# Schematic1_2.net
KiCad netlist of a schematic drawn in Altium Designer
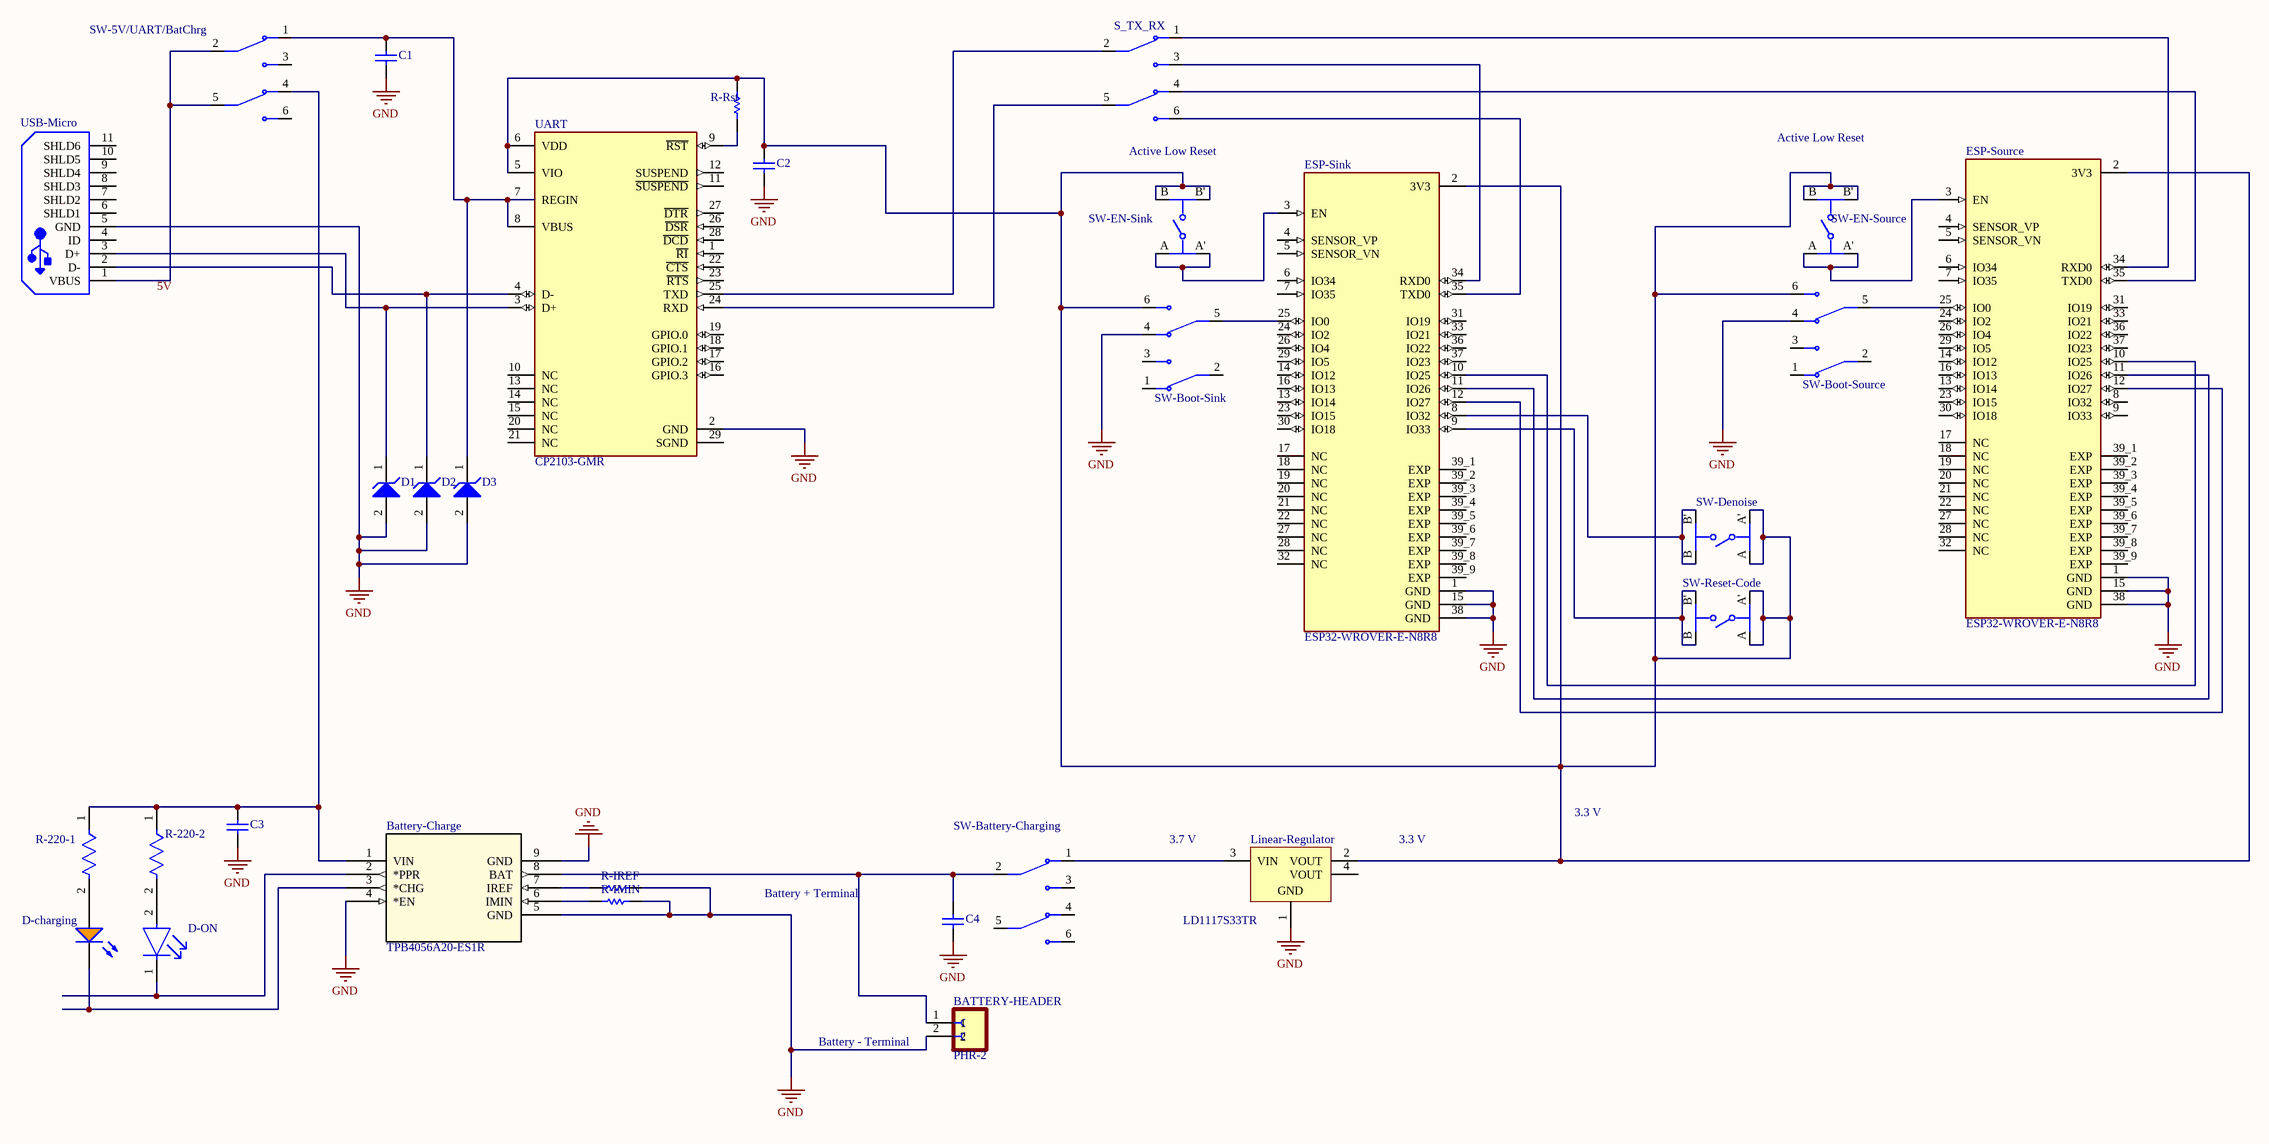
[diagram p0: Schematic1.2.SchDoc]

(export (version "E")
  (design (tool "Eeschema 10.0.6"))
  (components
    (comp (ref "Battery-Charge")
      (value "TPB4056A20-ES1R")
      (footprint "ESOP-8_TPK")
      (description "No Description Available")
      (libsource (lib "TPB4056A20-ES1R") (part "TPB4056A20-ES1R"))
    )
    (comp (ref "BATTERY-HEADER")
      (value "PHR-2")
      (footprint "FP-PHR-2-MFG")
      (description "PH Series 2 Position 2 mm Pitch Free Hanging Housing Connector")
      (libsource (lib "Ninos Rihan") (part "PHR-2"))
    )
    (comp (ref "C1")
      (value "C0603C105K3RACTU")
      (footprint "CAPC1608X87X35LL15T15")
      (fields (field (name "MANUFACTURER") "Kemet"))
      (libsource (lib "Altium Content Vault") (part "CAP"))
    )
    (comp (ref "C2")
      (value "C0603C105K3RACTU")
      (footprint "CAPC1608X87X35LL15T15")
      (fields (field (name "MANUFACTURER") "Kemet"))
      (libsource (lib "Altium Content Vault") (part "CAP"))
    )
    (comp (ref "C3")
      (value "C0603C105K3RACTU")
      (footprint "CAPC1608X87X35LL15T15")
      (fields (field (name "MANUFACTURER") "Kemet"))
      (libsource (lib "Altium Content Vault") (part "CAP"))
    )
    (comp (ref "C4")
      (value "C0603C105K3RACTU")
      (footprint "CAPC1608X87X35LL15T15")
      (fields (field (name "MANUFACTURER") "Kemet"))
      (libsource (lib "Altium Content Vault") (part "CAP"))
    )
    (comp (ref "D-charging")
      (value "LTST-C190AKT")
      (footprint "LTST-C190AKT-2_V")
      (description "Single Color Chip LED, 2.1 V, 2 mcd, -55 to 85 degC, 2-Pin SMD, RoHS, Tape and Reel")
      (libsource (lib "Altium Content Vault") (part "LED-ORANGE-AK-2"))
    )
    (comp (ref "D-ON")
      (value "LTST-C190GKT")
      (footprint "FP-LTST-C190GKT-MFG")
      (description "LED GREEN CLEAR CHIP SMD")
      (fields (field (name "VOLTAGE") "2V"))
      (libsource (lib "Altium Content Vault") (part "8706943c75ba83719d021d2fdc84c58"))
    )
    (comp (ref "D1")
      (value "MMSZ4691T1G")
      (footprint "ONSC-SOD-123-2-425-04_V")
      (description "Zener Voltage Regulator, 500 mW, 2-Pin SOD-123, Pb-Free, Tape and Reel")
      (fields (field (name "MANUFACTURER") "On Semiconductor"))
      (libsource (lib "Altium Content Vault") (part "ONSC-K1A2-2"))
    )
    (comp (ref "D2")
      (value "MMSZ4691T1G")
      (footprint "ONSC-SOD-123-2-425-04_V")
      (description "Zener Voltage Regulator, 500 mW, 2-Pin SOD-123, Pb-Free, Tape and Reel")
      (fields (field (name "MANUFACTURER") "On Semiconductor"))
      (libsource (lib "Altium Content Vault") (part "ONSC-K1A2-2"))
    )
    (comp (ref "D3")
      (value "MMSZ4691T1G")
      (footprint "ONSC-SOD-123-2-425-04_V")
      (description "Zener Voltage Regulator, 500 mW, 2-Pin SOD-123, Pb-Free, Tape and Reel")
      (fields (field (name "MANUFACTURER") "On Semiconductor"))
      (libsource (lib "Altium Content Vault") (part "ONSC-K1A2-2"))
    )
    (comp (ref "ESP-Sink")
      (value "ESP32-WROVER-E-N8R8")
      (footprint "XCVR_ESP32-WROVER-E-N8R8")
      (libsource (lib "Ninos Rihan") (part "ESP32-WROVER-E-N8R8"))
    )
    (comp (ref "ESP-Source")
      (value "ESP32-WROVER-E-N8R8")
      (footprint "XCVR_ESP32-WROVER-E-N8R8")
      (libsource (lib "Ninos Rihan") (part "ESP32-WROVER-E-N8R8"))
    )
    (comp (ref "Linear-Regulator")
      (value "LD1117S33TR")
      (footprint "SOT-223_L")
      (description "Fixed Low Drop Positive Voltage Regulator, 3.3V, 4-Pin SOT-223, Tape and Reel")
      (libsource (lib "Altium Content Vault") (part "PM-REG-LD1117-SOT4"))
    )
    (comp (ref "R-220-1")
      (value "CRCW0603220RFKEA")
      (footprint "FP-CRCW0603-e3-MFG")
      (description "RES Thick Film, 220Ω, 1%, 0.1W, 100ppm/°C, 0603")
      (fields (field (name "TOLERANCE") "1%"))
      (libsource (lib "Altium Content Vault") (part "1029c3af85768c4190bb7ad29bc67b5"))
    )
    (comp (ref "R-220-2")
      (value "CRCW0603220RFKEA")
      (footprint "FP-CRCW0603-e3-MFG")
      (description "RES Thick Film, 220Ω, 1%, 0.1W, 100ppm/°C, 0603")
      (fields (field (name "TOLERANCE") "1%"))
      (libsource (lib "Altium Content Vault") (part "1029c3af85768c4190bb7ad29bc67b5"))
    )
    (comp (ref "R-IMIN")
      (value "CRCW0805100KJNEA")
      (footprint "RESC2013X50X30ML20T20")
      (fields
        (field (name "MANUFACTURER") "Vishay Dale")
        (field (name "TOLERANCE") "5%")
        (field (name "POWER") "125mW")
      )
      (libsource (lib "Altium Content Vault") (part "RES"))
    )
    (comp (ref "R-IREF")
      (value "ERJ-3EKF1301V")
      (footprint "RESC1608X55X30NL15T15")
      (fields
        (field (name "MANUFACTURER") "Panasonic")
        (field (name "TOLERANCE") "1%")
        (field (name "POWER") "100mW")
      )
      (libsource (lib "Altium Content Vault") (part "RES"))
    )
    (comp (ref "R-Rst")
      (value "RC0603FR-074K7L")
      (footprint "RESC1608X55X25LL10T15")
      (description "Chip Resistor, 4.7 KOhm, +/- 1%, 0.1 W, -55 to 155 degC, 0603 (1608 Metric), RoHS, Tape and Reel")
      (fields (field (name "MANUFACTURER") "Yageo") (field (name "TOLERANCE") "1%"))
      (libsource (lib "Altium Content Vault") (part "RES-2"))
    )
    (comp (ref "SW-5V/UART/BatChrg")
      (value "SLW-913535-2A-SMT")
      (footprint "SW_SLW-913535-2A-SMT")
      (description "Switch Slide ON ON DPDT Raised Slide 0.1A 12VDC 10000Cycles Gull Wing SMD Box")
      (libsource (lib "Ninos Rihan") (part "SLW-913535-2A-SMT"))
    )
    (comp (ref "SW-Battery-Charging")
      (value "SLW-913535-2A-SMT")
      (footprint "SW_SLW-913535-2A-SMT")
      (description "Switch Slide ON ON DPDT Raised Slide 0.1A 12VDC 10000Cycles Gull Wing SMD Box")
      (libsource (lib "Ninos Rihan") (part "SLW-913535-2A-SMT"))
    )
    (comp (ref "SW-Boot-Sink")
      (value "SLW-913535-2A-SMT")
      (footprint "SW_SLW-913535-2A-SMT")
      (description "Switch Slide ON ON DPDT Raised Slide 0.1A 12VDC 10000Cycles Gull Wing SMD Box")
      (libsource (lib "Ninos Rihan") (part "SLW-913535-2A-SMT"))
    )
    (comp (ref "SW-Boot-Source")
      (value "SLW-913535-2A-SMT")
      (footprint "SW_SLW-913535-2A-SMT")
      (description "Switch Slide ON ON DPDT Raised Slide 0.1A 12VDC 10000Cycles Gull Wing SMD Box")
      (libsource (lib "Ninos Rihan") (part "SLW-913535-2A-SMT"))
    )
    (comp (ref "SW-Denoise")
      (value "EVQ-Q2F03W")
      (footprint "FP-EVQ-Q2F03W-MFG")
      (description "SWITCH TACTILE SPST-NO 0.02A 15V")
      (libsource (lib "Altium Content Vault") (part "9677229990528492022b31d4503349f"))
    )
    (comp (ref "SW-EN-Sink")
      (value "EVQ-Q2F03W")
      (footprint "FP-EVQ-Q2F03W-MFG")
      (description "SWITCH TACTILE SPST-NO 0.02A 15V")
      (libsource (lib "Altium Content Vault") (part "9677229990528492022b31d4503349f"))
    )
    (comp (ref "SW-EN-Source")
      (value "EVQ-Q2F03W")
      (footprint "FP-EVQ-Q2F03W-MFG")
      (description "SWITCH TACTILE SPST-NO 0.02A 15V")
      (libsource (lib "Altium Content Vault") (part "9677229990528492022b31d4503349f"))
    )
    (comp (ref "SW-Reset-Code")
      (value "EVQ-Q2F03W")
      (footprint "FP-EVQ-Q2F03W-MFG")
      (description "SWITCH TACTILE SPST-NO 0.02A 15V")
      (libsource (lib "Altium Content Vault") (part "9677229990528492022b31d4503349f"))
    )
    (comp (ref "S_TX_RX")
      (value "SLW-913535-2A-SMT")
      (footprint "SW_SLW-913535-2A-SMT")
      (description "Switch Slide ON ON DPDT Raised Slide 0.1A 12VDC 10000Cycles Gull Wing SMD Box")
      (libsource (lib "Ninos Rihan") (part "SLW-913535-2A-SMT"))
    )
    (comp (ref "UART")
      (value "CP2103-GMR")
      (footprint "FP-CP2103-GMR-MFG")
      (description "IC CTRLR BRIDGE USB-UART 28MLP")
      (fields
        (field (name "OCTOPART") "https://octopart.com/cp2103-gmr-silicon+labs-519938")
        (field (name "MANUFACTURER") "Silicon Labs")
      )
      (libsource (lib "Altium Content Vault") (part "a6f025e339dce55f038a892d75eb59b"))
    )
    (comp (ref "USB-Micro")
      (value "105017-0001")
      (footprint "USB-MICRO-B_V")
      (fields (field (name "MANUFACTURER") "Molex"))
      (libsource (lib "Altium Content Vault") (part "USB-5-6SHLD"))
    )
  )
  (nets
    (net (code "2") (name "GND") (class "Default")
      (node (ref "BATTERY-HEADER") (pin "2") (pinfunction "2_2") (pintype "passive"))
      (node (ref "Battery-Charge") (pin "4") (pinfunction "*EN_4") (pintype "input"))
      (node (ref "Battery-Charge") (pin "5") (pinfunction "GND_5") (pintype "power_in"))
      (node (ref "Battery-Charge") (pin "9") (pinfunction "GND_9") (pintype "power_in"))
      (node (ref "C1") (pin "1") (pinfunction "1_1") (pintype "passive"))
      (node (ref "C2") (pin "1") (pinfunction "1_1") (pintype "passive"))
      (node (ref "C3") (pin "1") (pinfunction "1_1") (pintype "passive"))
      (node (ref "C4") (pin "1") (pinfunction "1_1") (pintype "passive"))
      (node (ref "D1") (pin "2") (pinfunction "A_2") (pintype "passive"))
      (node (ref "D2") (pin "2") (pinfunction "A_2") (pintype "passive"))
      (node (ref "D3") (pin "2") (pinfunction "A_2") (pintype "passive"))
      (node (ref "ESP-Sink") (pin "1") (pinfunction "GND_1") (pintype "power_in"))
      (node (ref "ESP-Sink") (pin "15") (pinfunction "GND_15") (pintype "power_in"))
      (node (ref "ESP-Sink") (pin "38") (pinfunction "GND_38") (pintype "power_in"))
      (node (ref "ESP-Source") (pin "1") (pinfunction "GND_1") (pintype "power_in"))
      (node (ref "ESP-Source") (pin "15") (pinfunction "GND_15") (pintype "power_in"))
      (node (ref "ESP-Source") (pin "38") (pinfunction "GND_38") (pintype "power_in"))
      (node (ref "Linear-Regulator") (pin "1") (pinfunction "GND_1") (pintype "power_in"))
      (node (ref "R-IMIN") (pin "2") (pinfunction "2_2") (pintype "passive"))
      (node (ref "R-IREF") (pin "2") (pinfunction "2_2") (pintype "passive"))
      (node (ref "SW-Boot-Sink") (pin "4") (pinfunction "4_4") (pintype "passive"))
      (node (ref "SW-Boot-Source") (pin "4") (pinfunction "4_4") (pintype "passive"))
      (node (ref "UART") (pin "2") (pinfunction "GND_2") (pintype "power_in"))
      (node (ref "USB-Micro") (pin "5") (pinfunction "GND_5") (pintype "passive"))
    )
    (net (code "3") (name "Net-(Battery-Charge-*CHG)") (class "Default")
      (node (ref "Battery-Charge") (pin "3") (pinfunction "*CHG_3") (pintype "output"))
      (node (ref "D-charging") (pin "2") (pinfunction "K_2") (pintype "passive"))
    )
    (net (code "4") (name "Net-(Battery-Charge-*PPR)") (class "Default")
      (node (ref "Battery-Charge") (pin "2") (pinfunction "*PPR_2") (pintype "output"))
      (node (ref "D-ON") (pin "1") (pinfunction "C_1") (pintype "passive"))
    )
    (net (code "5") (name "Net-(Battery-Charge-BAT)") (class "Default")
      (node (ref "BATTERY-HEADER") (pin "1") (pinfunction "1_1") (pintype "passive"))
      (node (ref "Battery-Charge") (pin "8") (pinfunction "BAT_8") (pintype "output"))
      (node (ref "C4") (pin "2") (pinfunction "2_2") (pintype "passive"))
      (node (ref "SW-Battery-Charging") (pin "2") (pinfunction "2_2") (pintype "passive"))
    )
    (net (code "6") (name "Net-(Battery-Charge-IMIN)") (class "Default")
      (node (ref "Battery-Charge") (pin "6") (pinfunction "IMIN_6") (pintype "input"))
      (node (ref "R-IMIN") (pin "1") (pinfunction "1_1") (pintype "passive"))
    )
    (net (code "7") (name "Net-(Battery-Charge-IREF)") (class "Default")
      (node (ref "Battery-Charge") (pin "7") (pinfunction "IREF_7") (pintype "input"))
      (node (ref "R-IREF") (pin "1") (pinfunction "1_1") (pintype "passive"))
    )
    (net (code "8") (name "Net-(Battery-Charge-VIN)") (class "Default")
      (node (ref "Battery-Charge") (pin "1") (pinfunction "VIN_1") (pintype "power_in"))
      (node (ref "C3") (pin "2") (pinfunction "2_2") (pintype "passive"))
      (node (ref "R-220-1") (pin "1") (pinfunction "1_1") (pintype "passive"))
      (node (ref "R-220-2") (pin "1") (pinfunction "1_1") (pintype "passive"))
      (node (ref "SW-5V/UART/BatChrg") (pin "4") (pinfunction "4_4") (pintype "passive"))
    )
    (net (code "9") (name "Net-(D-ON-A)") (class "Default")
      (node (ref "D-ON") (pin "2") (pinfunction "A_2") (pintype "passive"))
      (node (ref "R-220-2") (pin "2") (pinfunction "2_2") (pintype "passive"))
    )
    (net (code "10") (name "Net-(D-charging-A)") (class "Default")
      (node (ref "D-charging") (pin "1") (pinfunction "A_1") (pintype "passive"))
      (node (ref "R-220-1") (pin "2") (pinfunction "2_2") (pintype "passive"))
    )
    (net (code "11") (name "Net-(D1-K)") (class "Default")
      (node (ref "D1") (pin "1") (pinfunction "K_1") (pintype "passive"))
      (node (ref "UART") (pin "3") (pinfunction "D+_3") (pintype "bidirectional"))
      (node (ref "USB-Micro") (pin "3") (pinfunction "D+_3") (pintype "passive"))
    )
    (net (code "12") (name "Net-(D2-K)") (class "Default")
      (node (ref "D2") (pin "1") (pinfunction "K_1") (pintype "passive"))
      (node (ref "UART") (pin "4") (pinfunction "D-_4") (pintype "bidirectional"))
      (node (ref "USB-Micro") (pin "2") (pinfunction "D-_2") (pintype "passive"))
    )
    (net (code "13") (name "Net-(D3-K)") (class "Default")
      (node (ref "C1") (pin "2") (pinfunction "2_2") (pintype "passive"))
      (node (ref "D3") (pin "1") (pinfunction "K_1") (pintype "passive"))
      (node (ref "SW-5V/UART/BatChrg") (pin "1") (pinfunction "1_1") (pintype "passive"))
      (node (ref "UART") (pin "7") (pinfunction "REGIN_7") (pintype "power_in"))
      (node (ref "UART") (pin "8") (pinfunction "VBUS_8") (pintype "power_in"))
    )
    (net (code "14") (name "Net-(ESP-Sink-3V3)") (class "Default")
      (node (ref "C2") (pin "2") (pinfunction "2_2") (pintype "passive"))
      (node (ref "ESP-Sink") (pin "2") (pinfunction "3V3_2") (pintype "power_in"))
      (node (ref "ESP-Source") (pin "2") (pinfunction "3V3_2") (pintype "power_in"))
      (node (ref "Linear-Regulator") (pin "2") (pinfunction "VOUT_2") (pintype "power_in"))
      (node (ref "R-Rst") (pin "2") (pinfunction "2_2") (pintype "passive"))
      (node (ref "SW-Boot-Sink") (pin "6") (pinfunction "6_6") (pintype "passive"))
      (node (ref "SW-Boot-Source") (pin "6") (pinfunction "6_6") (pintype "passive"))
      (node (ref "SW-Denoise") (pin "A") (pinfunction "A_A") (pintype "passive"))
      (node (ref "SW-Denoise") (pin "A'") (pinfunction "A'_A'") (pintype "passive"))
      (node (ref "SW-EN-Sink") (pin "B") (pinfunction "B_B") (pintype "passive"))
      (node (ref "SW-EN-Sink") (pin "B'") (pinfunction "B'_B'") (pintype "passive"))
      (node (ref "SW-EN-Source") (pin "B") (pinfunction "B_B") (pintype "passive"))
      (node (ref "SW-EN-Source") (pin "B'") (pinfunction "B'_B'") (pintype "passive"))
      (node (ref "SW-Reset-Code") (pin "A") (pinfunction "A_A") (pintype "passive"))
      (node (ref "SW-Reset-Code") (pin "A'") (pinfunction "A'_A'") (pintype "passive"))
      (node (ref "UART") (pin "5") (pinfunction "VIO_5") (pintype "power_in"))
      (node (ref "UART") (pin "6") (pinfunction "VDD_6") (pintype "power_in"))
    )
    (net (code "15") (name "Net-(ESP-Sink-EN)") (class "Default")
      (node (ref "ESP-Sink") (pin "3") (pinfunction "EN_3") (pintype "input"))
      (node (ref "SW-EN-Sink") (pin "A") (pinfunction "A_A") (pintype "passive"))
      (node (ref "SW-EN-Sink") (pin "A'") (pinfunction "A'_A'") (pintype "passive"))
    )
    (net (code "16") (name "Net-(ESP-Sink-IO0)") (class "Default")
      (node (ref "ESP-Sink") (pin "25") (pinfunction "IO0_25") (pintype "bidirectional"))
      (node (ref "SW-Boot-Sink") (pin "5") (pinfunction "5_5") (pintype "passive"))
    )
    (net (code "17") (name "Net-(ESP-Sink-IO25)") (class "Default")
      (node (ref "ESP-Sink") (pin "10") (pinfunction "IO25_10") (pintype "bidirectional"))
      (node (ref "ESP-Source") (pin "10") (pinfunction "IO25_10") (pintype "bidirectional"))
    )
    (net (code "18") (name "Net-(ESP-Sink-IO26)") (class "Default")
      (node (ref "ESP-Sink") (pin "11") (pinfunction "IO26_11") (pintype "bidirectional"))
      (node (ref "ESP-Source") (pin "11") (pinfunction "IO26_11") (pintype "bidirectional"))
    )
    (net (code "19") (name "Net-(ESP-Sink-IO27)") (class "Default")
      (node (ref "ESP-Sink") (pin "12") (pinfunction "IO27_12") (pintype "bidirectional"))
      (node (ref "ESP-Source") (pin "12") (pinfunction "IO27_12") (pintype "bidirectional"))
    )
    (net (code "20") (name "Net-(ESP-Sink-IO32)") (class "Default")
      (node (ref "ESP-Sink") (pin "8") (pinfunction "IO32_8") (pintype "bidirectional"))
      (node (ref "SW-Denoise") (pin "B") (pinfunction "B_B") (pintype "passive"))
      (node (ref "SW-Denoise") (pin "B'") (pinfunction "B'_B'") (pintype "passive"))
    )
    (net (code "21") (name "Net-(ESP-Sink-IO33)") (class "Default")
      (node (ref "ESP-Sink") (pin "9") (pinfunction "IO33_9") (pintype "bidirectional"))
      (node (ref "SW-Reset-Code") (pin "B") (pinfunction "B_B") (pintype "passive"))
      (node (ref "SW-Reset-Code") (pin "B'") (pinfunction "B'_B'") (pintype "passive"))
    )
    (net (code "22") (name "Net-(ESP-Sink-RXD0)") (class "Default")
      (node (ref "ESP-Sink") (pin "34") (pinfunction "RXD0_34") (pintype "bidirectional"))
      (node (ref "S_TX_RX") (pin "3") (pinfunction "3_3") (pintype "passive"))
    )
    (net (code "23") (name "Net-(ESP-Sink-TXD0)") (class "Default")
      (node (ref "ESP-Sink") (pin "35") (pinfunction "TXD0_35") (pintype "bidirectional"))
      (node (ref "S_TX_RX") (pin "6") (pinfunction "6_6") (pintype "passive"))
    )
    (net (code "24") (name "Net-(ESP-Source-EN)") (class "Default")
      (node (ref "ESP-Source") (pin "3") (pinfunction "EN_3") (pintype "input"))
      (node (ref "SW-EN-Source") (pin "A") (pinfunction "A_A") (pintype "passive"))
      (node (ref "SW-EN-Source") (pin "A'") (pinfunction "A'_A'") (pintype "passive"))
    )
    (net (code "25") (name "Net-(ESP-Source-IO0)") (class "Default")
      (node (ref "ESP-Source") (pin "25") (pinfunction "IO0_25") (pintype "bidirectional"))
      (node (ref "SW-Boot-Source") (pin "5") (pinfunction "5_5") (pintype "passive"))
    )
    (net (code "26") (name "Net-(ESP-Source-RXD0)") (class "Default")
      (node (ref "ESP-Source") (pin "34") (pinfunction "RXD0_34") (pintype "bidirectional"))
      (node (ref "S_TX_RX") (pin "1") (pinfunction "1_1") (pintype "passive"))
    )
    (net (code "27") (name "Net-(ESP-Source-TXD0)") (class "Default")
      (node (ref "ESP-Source") (pin "35") (pinfunction "TXD0_35") (pintype "bidirectional"))
      (node (ref "S_TX_RX") (pin "4") (pinfunction "4_4") (pintype "passive"))
    )
    (net (code "28") (name "Net-(Linear-Regulator-VIN)") (class "Default")
      (node (ref "Linear-Regulator") (pin "3") (pinfunction "VIN_3") (pintype "power_in"))
      (node (ref "SW-Battery-Charging") (pin "1") (pinfunction "1_1") (pintype "passive"))
    )
    (net (code "29") (name "Net-(UART-RXD)") (class "Default")
      (node (ref "S_TX_RX") (pin "5") (pinfunction "5_5") (pintype "passive"))
      (node (ref "UART") (pin "24") (pinfunction "RXD_24") (pintype "input"))
    )
    (net (code "30") (name "Net-(UART-TXD)") (class "Default")
      (node (ref "S_TX_RX") (pin "2") (pinfunction "2_2") (pintype "passive"))
      (node (ref "UART") (pin "25") (pinfunction "TXD_25") (pintype "output"))
    )
    (net (code "31") (name "Net-(UART-~{RST})") (class "Default")
      (node (ref "R-Rst") (pin "1") (pinfunction "1_1") (pintype "passive"))
      (node (ref "UART") (pin "9") (pinfunction "~{RST}_9") (pintype "bidirectional"))
    )
    (net (code "32") (name "Net-(USB-Micro-VBUS)") (class "Default")
      (node (ref "SW-5V/UART/BatChrg") (pin "2") (pinfunction "2_2") (pintype "passive"))
      (node (ref "SW-5V/UART/BatChrg") (pin "5") (pinfunction "5_5") (pintype "passive"))
      (node (ref "USB-Micro") (pin "1") (pinfunction "VBUS_1") (pintype "passive"))
    )
    (net (code "33") (name "unconnected-(ESP-Sink-EXP-Pad39_1)") (class "Default")
      (node (ref "ESP-Sink") (pin "39_1") (pinfunction "EXP_39_1") (pintype "power_in"))
    )
    (net (code "34") (name "unconnected-(ESP-Sink-EXP-Pad39_2)") (class "Default")
      (node (ref "ESP-Sink") (pin "39_2") (pinfunction "EXP_39_2") (pintype "power_in"))
    )
    (net (code "35") (name "unconnected-(ESP-Sink-EXP-Pad39_3)") (class "Default")
      (node (ref "ESP-Sink") (pin "39_3") (pinfunction "EXP_39_3") (pintype "power_in"))
    )
    (net (code "36") (name "unconnected-(ESP-Sink-EXP-Pad39_4)") (class "Default")
      (node (ref "ESP-Sink") (pin "39_4") (pinfunction "EXP_39_4") (pintype "power_in"))
    )
    (net (code "37") (name "unconnected-(ESP-Sink-EXP-Pad39_5)") (class "Default")
      (node (ref "ESP-Sink") (pin "39_5") (pinfunction "EXP_39_5") (pintype "power_in"))
    )
    (net (code "38") (name "unconnected-(ESP-Sink-EXP-Pad39_6)") (class "Default")
      (node (ref "ESP-Sink") (pin "39_6") (pinfunction "EXP_39_6") (pintype "power_in"))
    )
    (net (code "39") (name "unconnected-(ESP-Sink-EXP-Pad39_7)") (class "Default")
      (node (ref "ESP-Sink") (pin "39_7") (pinfunction "EXP_39_7") (pintype "power_in"))
    )
    (net (code "40") (name "unconnected-(ESP-Sink-EXP-Pad39_8)") (class "Default")
      (node (ref "ESP-Sink") (pin "39_8") (pinfunction "EXP_39_8") (pintype "power_in"))
    )
    (net (code "41") (name "unconnected-(ESP-Sink-EXP-Pad39_9)") (class "Default")
      (node (ref "ESP-Sink") (pin "39_9") (pinfunction "EXP_39_9") (pintype "power_in"))
    )
    (net (code "42") (name "unconnected-(ESP-Sink-IO2-Pad24)") (class "Default")
      (node (ref "ESP-Sink") (pin "24") (pinfunction "IO2_24") (pintype "bidirectional"))
    )
    (net (code "43") (name "unconnected-(ESP-Sink-IO4-Pad26)") (class "Default")
      (node (ref "ESP-Sink") (pin "26") (pinfunction "IO4_26") (pintype "bidirectional"))
    )
    (net (code "44") (name "unconnected-(ESP-Sink-IO5-Pad29)") (class "Default")
      (node (ref "ESP-Sink") (pin "29") (pinfunction "IO5_29") (pintype "bidirectional"))
    )
    (net (code "45") (name "unconnected-(ESP-Sink-IO12-Pad14)") (class "Default")
      (node (ref "ESP-Sink") (pin "14") (pinfunction "IO12_14") (pintype "bidirectional"))
    )
    (net (code "46") (name "unconnected-(ESP-Sink-IO13-Pad16)") (class "Default")
      (node (ref "ESP-Sink") (pin "16") (pinfunction "IO13_16") (pintype "bidirectional"))
    )
    (net (code "47") (name "unconnected-(ESP-Sink-IO14-Pad13)") (class "Default")
      (node (ref "ESP-Sink") (pin "13") (pinfunction "IO14_13") (pintype "bidirectional"))
    )
    (net (code "48") (name "unconnected-(ESP-Sink-IO15-Pad23)") (class "Default")
      (node (ref "ESP-Sink") (pin "23") (pinfunction "IO15_23") (pintype "bidirectional"))
    )
    (net (code "49") (name "unconnected-(ESP-Sink-IO18-Pad30)") (class "Default")
      (node (ref "ESP-Sink") (pin "30") (pinfunction "IO18_30") (pintype "bidirectional"))
    )
    (net (code "50") (name "unconnected-(ESP-Sink-IO19-Pad31)") (class "Default")
      (node (ref "ESP-Sink") (pin "31") (pinfunction "IO19_31") (pintype "bidirectional"))
    )
    (net (code "51") (name "unconnected-(ESP-Sink-IO21-Pad33)") (class "Default")
      (node (ref "ESP-Sink") (pin "33") (pinfunction "IO21_33") (pintype "bidirectional"))
    )
    (net (code "52") (name "unconnected-(ESP-Sink-IO22-Pad36)") (class "Default")
      (node (ref "ESP-Sink") (pin "36") (pinfunction "IO22_36") (pintype "bidirectional"))
    )
    (net (code "53") (name "unconnected-(ESP-Sink-IO23-Pad37)") (class "Default")
      (node (ref "ESP-Sink") (pin "37") (pinfunction "IO23_37") (pintype "bidirectional"))
    )
    (net (code "54") (name "unconnected-(ESP-Sink-IO34-Pad6)") (class "Default")
      (node (ref "ESP-Sink") (pin "6") (pinfunction "IO34_6") (pintype "input"))
    )
    (net (code "55") (name "unconnected-(ESP-Sink-IO35-Pad7)") (class "Default")
      (node (ref "ESP-Sink") (pin "7") (pinfunction "IO35_7") (pintype "input"))
    )
    (net (code "56") (name "unconnected-(ESP-Sink-NC-Pad17)") (class "Default")
      (node (ref "ESP-Sink") (pin "17") (pinfunction "NC_17") (pintype "passive"))
    )
    (net (code "57") (name "unconnected-(ESP-Sink-NC-Pad18)") (class "Default")
      (node (ref "ESP-Sink") (pin "18") (pinfunction "NC_18") (pintype "passive"))
    )
    (net (code "58") (name "unconnected-(ESP-Sink-NC-Pad19)") (class "Default")
      (node (ref "ESP-Sink") (pin "19") (pinfunction "NC_19") (pintype "passive"))
    )
    (net (code "59") (name "unconnected-(ESP-Sink-NC-Pad20)") (class "Default")
      (node (ref "ESP-Sink") (pin "20") (pinfunction "NC_20") (pintype "passive"))
    )
    (net (code "60") (name "unconnected-(ESP-Sink-NC-Pad21)") (class "Default")
      (node (ref "ESP-Sink") (pin "21") (pinfunction "NC_21") (pintype "passive"))
    )
    (net (code "61") (name "unconnected-(ESP-Sink-NC-Pad22)") (class "Default")
      (node (ref "ESP-Sink") (pin "22") (pinfunction "NC_22") (pintype "passive"))
    )
    (net (code "62") (name "unconnected-(ESP-Sink-NC-Pad27)") (class "Default")
      (node (ref "ESP-Sink") (pin "27") (pinfunction "NC_27") (pintype "passive"))
    )
    (net (code "63") (name "unconnected-(ESP-Sink-NC-Pad28)") (class "Default")
      (node (ref "ESP-Sink") (pin "28") (pinfunction "NC_28") (pintype "passive"))
    )
    (net (code "64") (name "unconnected-(ESP-Sink-NC-Pad32)") (class "Default")
      (node (ref "ESP-Sink") (pin "32") (pinfunction "NC_32") (pintype "passive"))
    )
    (net (code "65") (name "unconnected-(ESP-Sink-SENSOR_VN-Pad5)") (class "Default")
      (node (ref "ESP-Sink") (pin "5") (pinfunction "SENSOR_VN_5") (pintype "input"))
    )
    (net (code "66") (name "unconnected-(ESP-Sink-SENSOR_VP-Pad4)") (class "Default")
      (node (ref "ESP-Sink") (pin "4") (pinfunction "SENSOR_VP_4") (pintype "input"))
    )
    (net (code "67") (name "unconnected-(ESP-Source-EXP-Pad39_1)") (class "Default")
      (node (ref "ESP-Source") (pin "39_1") (pinfunction "EXP_39_1") (pintype "power_in"))
    )
    (net (code "68") (name "unconnected-(ESP-Source-EXP-Pad39_2)") (class "Default")
      (node (ref "ESP-Source") (pin "39_2") (pinfunction "EXP_39_2") (pintype "power_in"))
    )
    (net (code "69") (name "unconnected-(ESP-Source-EXP-Pad39_3)") (class "Default")
      (node (ref "ESP-Source") (pin "39_3") (pinfunction "EXP_39_3") (pintype "power_in"))
    )
    (net (code "70") (name "unconnected-(ESP-Source-EXP-Pad39_4)") (class "Default")
      (node (ref "ESP-Source") (pin "39_4") (pinfunction "EXP_39_4") (pintype "power_in"))
    )
    (net (code "71") (name "unconnected-(ESP-Source-EXP-Pad39_5)") (class "Default")
      (node (ref "ESP-Source") (pin "39_5") (pinfunction "EXP_39_5") (pintype "power_in"))
    )
    (net (code "72") (name "unconnected-(ESP-Source-EXP-Pad39_6)") (class "Default")
      (node (ref "ESP-Source") (pin "39_6") (pinfunction "EXP_39_6") (pintype "power_in"))
    )
    (net (code "73") (name "unconnected-(ESP-Source-EXP-Pad39_7)") (class "Default")
      (node (ref "ESP-Source") (pin "39_7") (pinfunction "EXP_39_7") (pintype "power_in"))
    )
    (net (code "74") (name "unconnected-(ESP-Source-EXP-Pad39_8)") (class "Default")
      (node (ref "ESP-Source") (pin "39_8") (pinfunction "EXP_39_8") (pintype "power_in"))
    )
    (net (code "75") (name "unconnected-(ESP-Source-EXP-Pad39_9)") (class "Default")
      (node (ref "ESP-Source") (pin "39_9") (pinfunction "EXP_39_9") (pintype "power_in"))
    )
    (net (code "76") (name "unconnected-(ESP-Source-IO2-Pad24)") (class "Default")
      (node (ref "ESP-Source") (pin "24") (pinfunction "IO2_24") (pintype "bidirectional"))
    )
    (net (code "77") (name "unconnected-(ESP-Source-IO4-Pad26)") (class "Default")
      (node (ref "ESP-Source") (pin "26") (pinfunction "IO4_26") (pintype "bidirectional"))
    )
    (net (code "78") (name "unconnected-(ESP-Source-IO5-Pad29)") (class "Default")
      (node (ref "ESP-Source") (pin "29") (pinfunction "IO5_29") (pintype "bidirectional"))
    )
    (net (code "79") (name "unconnected-(ESP-Source-IO12-Pad14)") (class "Default")
      (node (ref "ESP-Source") (pin "14") (pinfunction "IO12_14") (pintype "bidirectional"))
    )
    (net (code "80") (name "unconnected-(ESP-Source-IO13-Pad16)") (class "Default")
      (node (ref "ESP-Source") (pin "16") (pinfunction "IO13_16") (pintype "bidirectional"))
    )
    (net (code "81") (name "unconnected-(ESP-Source-IO14-Pad13)") (class "Default")
      (node (ref "ESP-Source") (pin "13") (pinfunction "IO14_13") (pintype "bidirectional"))
    )
    (net (code "82") (name "unconnected-(ESP-Source-IO15-Pad23)") (class "Default")
      (node (ref "ESP-Source") (pin "23") (pinfunction "IO15_23") (pintype "bidirectional"))
    )
    (net (code "83") (name "unconnected-(ESP-Source-IO18-Pad30)") (class "Default")
      (node (ref "ESP-Source") (pin "30") (pinfunction "IO18_30") (pintype "bidirectional"))
    )
    (net (code "84") (name "unconnected-(ESP-Source-IO19-Pad31)") (class "Default")
      (node (ref "ESP-Source") (pin "31") (pinfunction "IO19_31") (pintype "bidirectional"))
    )
    (net (code "85") (name "unconnected-(ESP-Source-IO21-Pad33)") (class "Default")
      (node (ref "ESP-Source") (pin "33") (pinfunction "IO21_33") (pintype "bidirectional"))
    )
    (net (code "86") (name "unconnected-(ESP-Source-IO22-Pad36)") (class "Default")
      (node (ref "ESP-Source") (pin "36") (pinfunction "IO22_36") (pintype "bidirectional"))
    )
    (net (code "87") (name "unconnected-(ESP-Source-IO23-Pad37)") (class "Default")
      (node (ref "ESP-Source") (pin "37") (pinfunction "IO23_37") (pintype "bidirectional"))
    )
    (net (code "88") (name "unconnected-(ESP-Source-IO32-Pad8)") (class "Default")
      (node (ref "ESP-Source") (pin "8") (pinfunction "IO32_8") (pintype "bidirectional"))
    )
    (net (code "89") (name "unconnected-(ESP-Source-IO33-Pad9)") (class "Default")
      (node (ref "ESP-Source") (pin "9") (pinfunction "IO33_9") (pintype "bidirectional"))
    )
    (net (code "90") (name "unconnected-(ESP-Source-IO34-Pad6)") (class "Default")
      (node (ref "ESP-Source") (pin "6") (pinfunction "IO34_6") (pintype "input"))
    )
    (net (code "91") (name "unconnected-(ESP-Source-IO35-Pad7)") (class "Default")
      (node (ref "ESP-Source") (pin "7") (pinfunction "IO35_7") (pintype "input"))
    )
    (net (code "92") (name "unconnected-(ESP-Source-NC-Pad17)") (class "Default")
      (node (ref "ESP-Source") (pin "17") (pinfunction "NC_17") (pintype "passive"))
    )
    (net (code "93") (name "unconnected-(ESP-Source-NC-Pad18)") (class "Default")
      (node (ref "ESP-Source") (pin "18") (pinfunction "NC_18") (pintype "passive"))
    )
    (net (code "94") (name "unconnected-(ESP-Source-NC-Pad19)") (class "Default")
      (node (ref "ESP-Source") (pin "19") (pinfunction "NC_19") (pintype "passive"))
    )
    (net (code "95") (name "unconnected-(ESP-Source-NC-Pad20)") (class "Default")
      (node (ref "ESP-Source") (pin "20") (pinfunction "NC_20") (pintype "passive"))
    )
    (net (code "96") (name "unconnected-(ESP-Source-NC-Pad21)") (class "Default")
      (node (ref "ESP-Source") (pin "21") (pinfunction "NC_21") (pintype "passive"))
    )
    (net (code "97") (name "unconnected-(ESP-Source-NC-Pad22)") (class "Default")
      (node (ref "ESP-Source") (pin "22") (pinfunction "NC_22") (pintype "passive"))
    )
    (net (code "98") (name "unconnected-(ESP-Source-NC-Pad27)") (class "Default")
      (node (ref "ESP-Source") (pin "27") (pinfunction "NC_27") (pintype "passive"))
    )
    (net (code "99") (name "unconnected-(ESP-Source-NC-Pad28)") (class "Default")
      (node (ref "ESP-Source") (pin "28") (pinfunction "NC_28") (pintype "passive"))
    )
    (net (code "100") (name "unconnected-(ESP-Source-NC-Pad32)") (class "Default")
      (node (ref "ESP-Source") (pin "32") (pinfunction "NC_32") (pintype "passive"))
    )
    (net (code "101") (name "unconnected-(ESP-Source-SENSOR_VN-Pad5)") (class "Default")
      (node (ref "ESP-Source") (pin "5") (pinfunction "SENSOR_VN_5") (pintype "input"))
    )
    (net (code "102") (name "unconnected-(ESP-Source-SENSOR_VP-Pad4)") (class "Default")
      (node (ref "ESP-Source") (pin "4") (pinfunction "SENSOR_VP_4") (pintype "input"))
    )
    (net (code "103") (name "unconnected-(Linear-Regulator-VOUT-Pad4)") (class "Default")
      (node (ref "Linear-Regulator") (pin "4") (pinfunction "VOUT_4") (pintype "power_in"))
    )
    (net (code "104") (name "unconnected-(SW-5V/UART/BatChrg-Pad3)") (class "Default")
      (node (ref "SW-5V/UART/BatChrg") (pin "3") (pinfunction "3_3") (pintype "passive"))
    )
    (net (code "105") (name "unconnected-(SW-5V/UART/BatChrg-Pad6)") (class "Default")
      (node (ref "SW-5V/UART/BatChrg") (pin "6") (pinfunction "6_6") (pintype "passive"))
    )
    (net (code "106") (name "unconnected-(SW-Battery-Charging-Pad3)") (class "Default")
      (node (ref "SW-Battery-Charging") (pin "3") (pinfunction "3_3") (pintype "passive"))
    )
    (net (code "107") (name "unconnected-(SW-Battery-Charging-Pad4)") (class "Default")
      (node (ref "SW-Battery-Charging") (pin "4") (pinfunction "4_4") (pintype "passive"))
    )
    (net (code "108") (name "unconnected-(SW-Battery-Charging-Pad5)") (class "Default")
      (node (ref "SW-Battery-Charging") (pin "5") (pinfunction "5_5") (pintype "passive"))
    )
    (net (code "109") (name "unconnected-(SW-Battery-Charging-Pad6)") (class "Default")
      (node (ref "SW-Battery-Charging") (pin "6") (pinfunction "6_6") (pintype "passive"))
    )
    (net (code "110") (name "unconnected-(SW-Boot-Sink-Pad1)") (class "Default")
      (node (ref "SW-Boot-Sink") (pin "1") (pinfunction "1_1") (pintype "passive"))
    )
    (net (code "111") (name "unconnected-(SW-Boot-Sink-Pad2)") (class "Default")
      (node (ref "SW-Boot-Sink") (pin "2") (pinfunction "2_2") (pintype "passive"))
    )
    (net (code "112") (name "unconnected-(SW-Boot-Sink-Pad3)") (class "Default")
      (node (ref "SW-Boot-Sink") (pin "3") (pinfunction "3_3") (pintype "passive"))
    )
    (net (code "113") (name "unconnected-(SW-Boot-Source-Pad1)") (class "Default")
      (node (ref "SW-Boot-Source") (pin "1") (pinfunction "1_1") (pintype "passive"))
    )
    (net (code "114") (name "unconnected-(SW-Boot-Source-Pad2)") (class "Default")
      (node (ref "SW-Boot-Source") (pin "2") (pinfunction "2_2") (pintype "passive"))
    )
    (net (code "115") (name "unconnected-(SW-Boot-Source-Pad3)") (class "Default")
      (node (ref "SW-Boot-Source") (pin "3") (pinfunction "3_3") (pintype "passive"))
    )
    (net (code "116") (name "unconnected-(UART-GPIO.0-Pad19)") (class "Default")
      (node (ref "UART") (pin "19") (pinfunction "GPIO.0_19") (pintype "bidirectional"))
    )
    (net (code "117") (name "unconnected-(UART-GPIO.1-Pad18)") (class "Default")
      (node (ref "UART") (pin "18") (pinfunction "GPIO.1_18") (pintype "bidirectional"))
    )
    (net (code "118") (name "unconnected-(UART-GPIO.2-Pad17)") (class "Default")
      (node (ref "UART") (pin "17") (pinfunction "GPIO.2_17") (pintype "bidirectional"))
    )
    (net (code "119") (name "unconnected-(UART-GPIO.3-Pad16)") (class "Default")
      (node (ref "UART") (pin "16") (pinfunction "GPIO.3_16") (pintype "bidirectional"))
    )
    (net (code "120") (name "unconnected-(UART-NC-Pad10)") (class "Default")
      (node (ref "UART") (pin "10") (pinfunction "NC_10") (pintype "passive"))
    )
    (net (code "121") (name "unconnected-(UART-NC-Pad13)") (class "Default")
      (node (ref "UART") (pin "13") (pinfunction "NC_13") (pintype "passive"))
    )
    (net (code "122") (name "unconnected-(UART-NC-Pad14)") (class "Default")
      (node (ref "UART") (pin "14") (pinfunction "NC_14") (pintype "passive"))
    )
    (net (code "123") (name "unconnected-(UART-NC-Pad15)") (class "Default")
      (node (ref "UART") (pin "15") (pinfunction "NC_15") (pintype "passive"))
    )
    (net (code "124") (name "unconnected-(UART-NC-Pad20)") (class "Default")
      (node (ref "UART") (pin "20") (pinfunction "NC_20") (pintype "passive"))
    )
    (net (code "125") (name "unconnected-(UART-NC-Pad21)") (class "Default")
      (node (ref "UART") (pin "21") (pinfunction "NC_21") (pintype "passive"))
    )
    (net (code "126") (name "unconnected-(UART-SGND-Pad29)") (class "Default")
      (node (ref "UART") (pin "29") (pinfunction "SGND_29") (pintype "power_in"))
    )
    (net (code "127") (name "unconnected-(UART-SUSPEND-Pad12)") (class "Default")
      (node (ref "UART") (pin "12") (pinfunction "SUSPEND_12") (pintype "output"))
    )
    (net (code "128") (name "unconnected-(UART-~{CTS}-Pad22)") (class "Default")
      (node (ref "UART") (pin "22") (pinfunction "~{CTS}_22") (pintype "input"))
    )
    (net (code "129") (name "unconnected-(UART-~{DCD}-Pad28)") (class "Default")
      (node (ref "UART") (pin "28") (pinfunction "~{DCD}_28") (pintype "input"))
    )
    (net (code "130") (name "unconnected-(UART-~{DSR}-Pad26)") (class "Default")
      (node (ref "UART") (pin "26") (pinfunction "~{DSR}_26") (pintype "input"))
    )
    (net (code "131") (name "unconnected-(UART-~{DTR}-Pad27)") (class "Default")
      (node (ref "UART") (pin "27") (pinfunction "~{DTR}_27") (pintype "output"))
    )
    (net (code "132") (name "unconnected-(UART-~{RI}-Pad1)") (class "Default")
      (node (ref "UART") (pin "1") (pinfunction "~{RI}_1") (pintype "input"))
    )
    (net (code "133") (name "unconnected-(UART-~{RTS}-Pad23)") (class "Default")
      (node (ref "UART") (pin "23") (pinfunction "~{RTS}_23") (pintype "output"))
    )
    (net (code "134") (name "unconnected-(UART-~{SUSPEND}-Pad11)") (class "Default")
      (node (ref "UART") (pin "11") (pinfunction "~{SUSPEND}_11") (pintype "output"))
    )
    (net (code "135") (name "unconnected-(USB-Micro-ID-Pad4)") (class "Default")
      (node (ref "USB-Micro") (pin "4") (pinfunction "ID_4") (pintype "passive"))
    )
    (net (code "136") (name "unconnected-(USB-Micro-SHLD1-Pad6)") (class "Default")
      (node (ref "USB-Micro") (pin "6") (pinfunction "SHLD1_6") (pintype "passive"))
    )
    (net (code "137") (name "unconnected-(USB-Micro-SHLD2-Pad7)") (class "Default")
      (node (ref "USB-Micro") (pin "7") (pinfunction "SHLD2_7") (pintype "passive"))
    )
    (net (code "138") (name "unconnected-(USB-Micro-SHLD3-Pad8)") (class "Default")
      (node (ref "USB-Micro") (pin "8") (pinfunction "SHLD3_8") (pintype "passive"))
    )
    (net (code "139") (name "unconnected-(USB-Micro-SHLD4-Pad9)") (class "Default")
      (node (ref "USB-Micro") (pin "9") (pinfunction "SHLD4_9") (pintype "passive"))
    )
    (net (code "140") (name "unconnected-(USB-Micro-SHLD5-Pad10)") (class "Default")
      (node (ref "USB-Micro") (pin "10") (pinfunction "SHLD5_10") (pintype "passive"))
    )
    (net (code "141") (name "unconnected-(USB-Micro-SHLD6-Pad11)") (class "Default")
      (node (ref "USB-Micro") (pin "11") (pinfunction "SHLD6_11") (pintype "passive"))
    )
  )
)
